# A704E.net
KiCad netlist of a schematic drawn in EAGLE
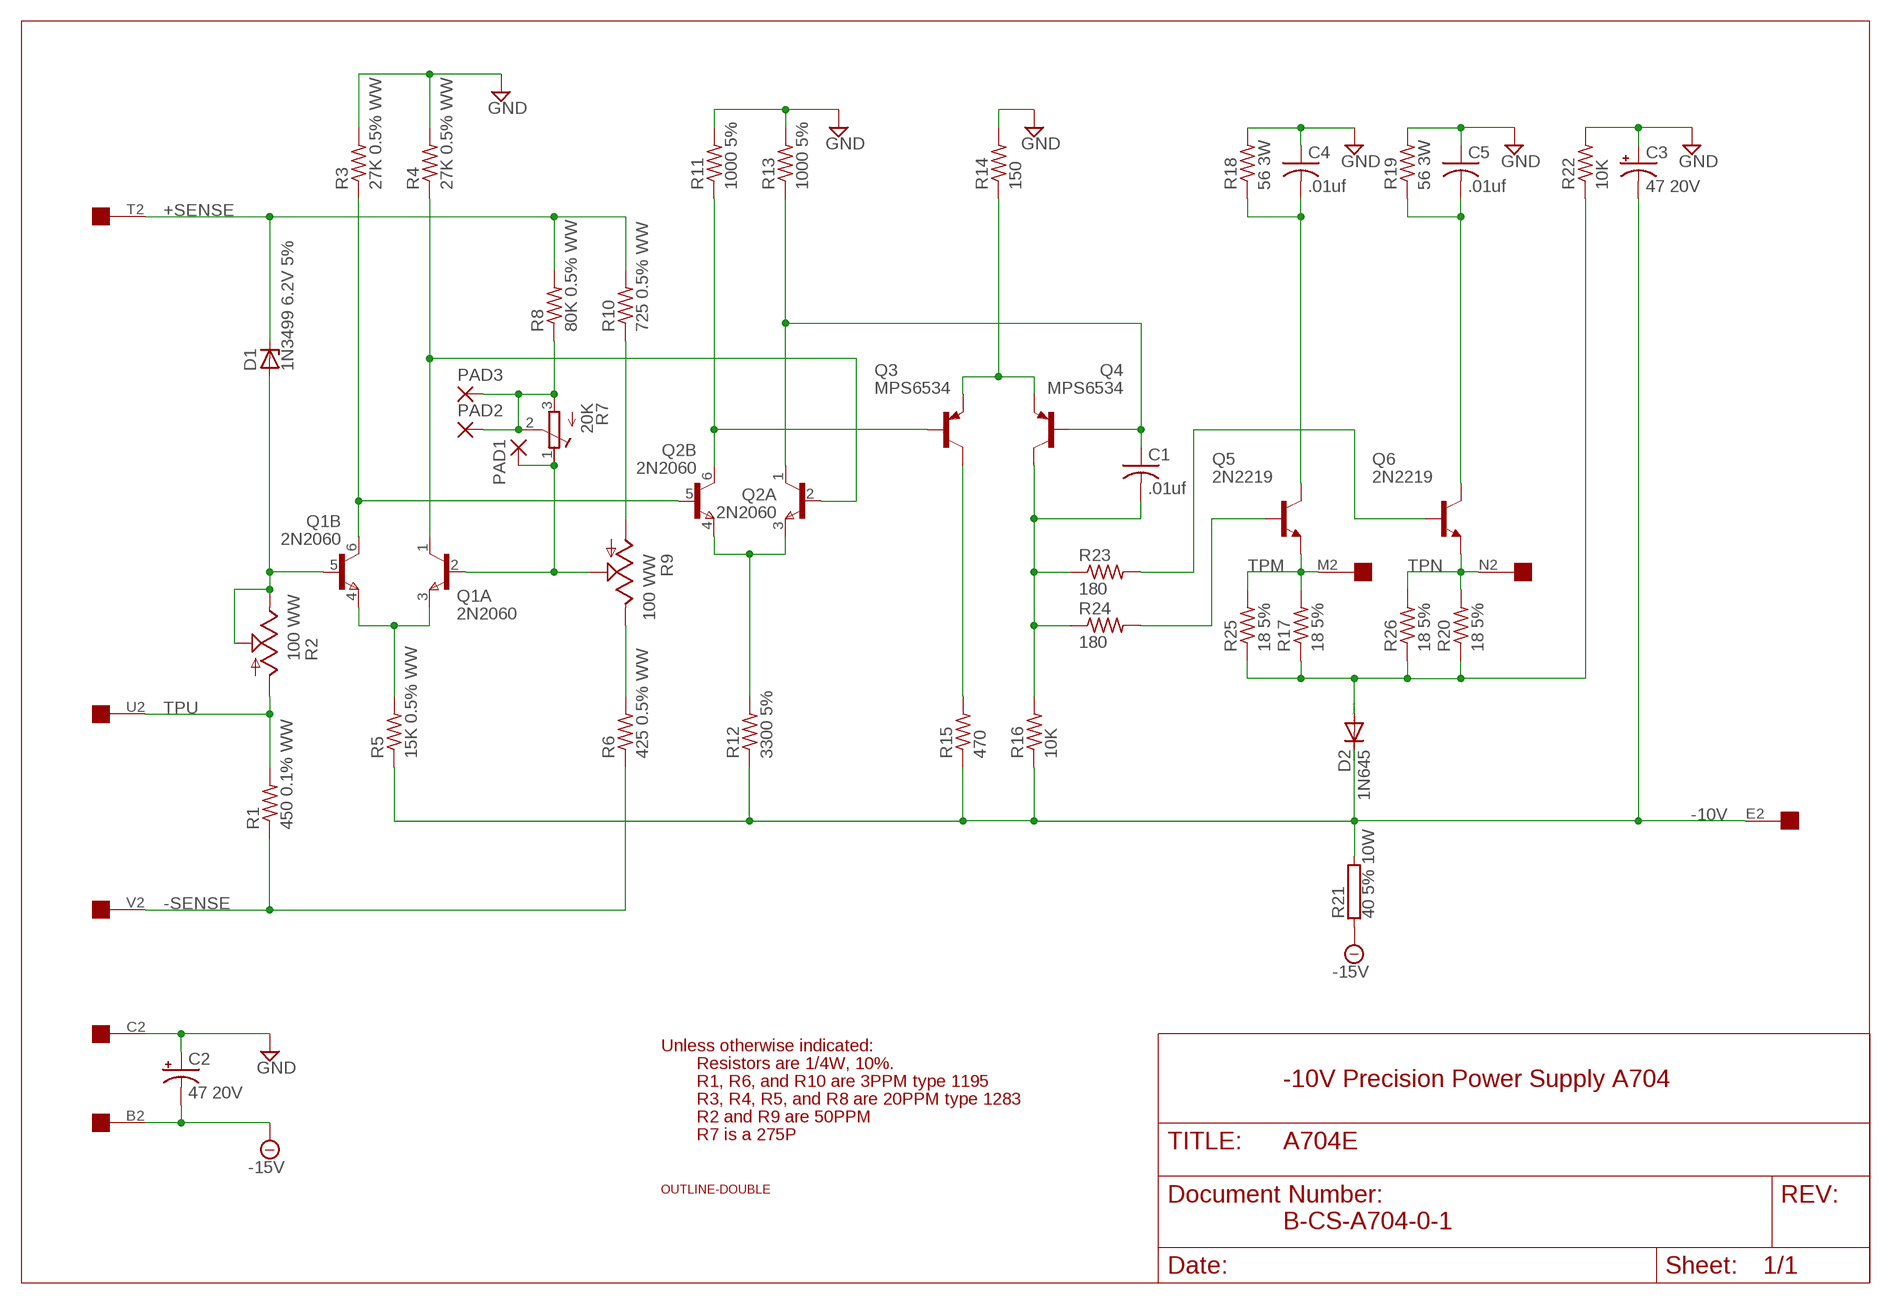
[diagram p0: schematic, sheet 1]

(export (version "E")
  (design (tool "Eeschema 10.0.6"))
  (components
    (comp (ref "C1")
      (value ".01uf")
      (footprint "eagle-import:C050-025X075")
      (libsource (lib "eagle-import") (part "C-US050-025X075"))
    )
    (comp (ref "C2")
      (value "47 20V")
      (footprint "eagle-import:E22-6")
      (libsource (lib "eagle-import") (part "CPOL-USE22-6AXIAL"))
    )
    (comp (ref "C3")
      (value "47 20V")
      (footprint "eagle-import:E22-6")
      (libsource (lib "eagle-import") (part "CPOL-USE22-6AXIAL"))
    )
    (comp (ref "C4")
      (value ".01uf")
      (footprint "eagle-import:C050-025X075")
      (libsource (lib "eagle-import") (part "C-US050-025X075"))
    )
    (comp (ref "C5")
      (value ".01uf")
      (footprint "eagle-import:C050-025X075")
      (libsource (lib "eagle-import") (part "C-US050-025X075"))
    )
    (comp (ref "D1")
      (value "1N3499 6.2V 5%")
      (footprint "eagle-import:DO35Z10")
      (libsource (lib "eagle-import") (part "ZENER-DIODEDO35Z10"))
    )
    (comp (ref "D2")
      (value "1N645")
      (footprint "eagle-import:DO35-10")
      (libsource (lib "eagle-import") (part "1N4148DO35-10"))
    )
    (comp (ref "PAD1")
      (value "2,54/1,0")
      (footprint "eagle-import:2,54_1,0")
      (libsource (lib "eagle-import") (part "2,54/1,0"))
    )
    (comp (ref "PAD2")
      (value "2,54/1,0")
      (footprint "eagle-import:2,54_1,0")
      (libsource (lib "eagle-import") (part "2,54/1,0"))
    )
    (comp (ref "PAD3")
      (value "2,54/1,0")
      (footprint "eagle-import:2,54_1,0")
      (libsource (lib "eagle-import") (part "2,54/1,0"))
    )
    (comp (ref "Q1")
      (value "2N2060")
      (footprint "eagle-import:TO78")
      (libsource (lib "eagle-import") (part "MAT-02H"))
    )
    (comp (ref "Q2")
      (value "2N2060")
      (footprint "eagle-import:TO78")
      (libsource (lib "eagle-import") (part "MAT-02H"))
    )
    (comp (ref "Q3")
      (value "MPS6534")
      (footprint "eagle-import:TO39")
      (libsource (lib "eagle-import") (part "2N2904A"))
    )
    (comp (ref "Q4")
      (value "MPS6534")
      (footprint "eagle-import:TO39")
      (libsource (lib "eagle-import") (part "2N2904A"))
    )
    (comp (ref "Q5")
      (value "2N2219")
      (footprint "eagle-import:TO39")
      (libsource (lib "eagle-import") (part "-NPN-TO39-EBC2N1613"))
    )
    (comp (ref "Q6")
      (value "2N2219")
      (footprint "eagle-import:TO39")
      (libsource (lib "eagle-import") (part "-NPN-TO39-EBC2N1613"))
    )
    (comp (ref "R1")
      (value "450 0.1% WW")
      (footprint "eagle-import:P0817_22")
      (libsource (lib "eagle-import") (part "R-US_0817/22"))
    )
    (comp (ref "R2")
      (value "100 WW")
      (footprint "eagle-import:S75P")
      (libsource (lib "eagle-import") (part "TRIM_US-S75P"))
    )
    (comp (ref "R3")
      (value "27K 0.5% WW")
      (footprint "eagle-import:0411_15")
      (libsource (lib "eagle-import") (part "R-US_0411/15"))
    )
    (comp (ref "R4")
      (value "27K 0.5% WW")
      (footprint "eagle-import:0411_15")
      (libsource (lib "eagle-import") (part "R-US_0411/15"))
    )
    (comp (ref "R5")
      (value "15K 0.5% WW")
      (footprint "eagle-import:0411_15")
      (libsource (lib "eagle-import") (part "R-US_0411/15"))
    )
    (comp (ref "R6")
      (value "425 0.5% WW")
      (footprint "eagle-import:P0817_22")
      (libsource (lib "eagle-import") (part "R-US_0817/22"))
    )
    (comp (ref "R7")
      (value "20K")
      (footprint "eagle-import:3006Y")
      (libsource (lib "eagle-import") (part "275P"))
    )
    (comp (ref "R8")
      (value "80K 0.5% WW")
      (footprint "eagle-import:0411_15")
      (libsource (lib "eagle-import") (part "R-US_0411/15"))
    )
    (comp (ref "R9")
      (value "100 WW")
      (footprint "eagle-import:S75P")
      (libsource (lib "eagle-import") (part "TRIM_US-S75P"))
    )
    (comp (ref "R10")
      (value "725 0.5% WW")
      (footprint "eagle-import:P0817_22")
      (libsource (lib "eagle-import") (part "R-US_0817/22"))
    )
    (comp (ref "R11")
      (value "1000 5%")
      (footprint "eagle-import:0207_10")
      (libsource (lib "eagle-import") (part "R-US_0207/10"))
    )
    (comp (ref "R12")
      (value "3300 5%")
      (footprint "eagle-import:0207_10")
      (libsource (lib "eagle-import") (part "R-US_0207/10"))
    )
    (comp (ref "R13")
      (value "1000 5%")
      (footprint "eagle-import:0207_10")
      (libsource (lib "eagle-import") (part "R-US_0207/10"))
    )
    (comp (ref "R14")
      (value "150")
      (footprint "eagle-import:0207_10")
      (libsource (lib "eagle-import") (part "R-US_0207/10"))
    )
    (comp (ref "R15")
      (value "470")
      (footprint "eagle-import:0207_10")
      (libsource (lib "eagle-import") (part "R-US_0207/10"))
    )
    (comp (ref "R16")
      (value "10K")
      (footprint "eagle-import:0207_10")
      (libsource (lib "eagle-import") (part "R-US_0207/10"))
    )
    (comp (ref "R17")
      (value "18 5%")
      (footprint "eagle-import:0207_10")
      (libsource (lib "eagle-import") (part "R-US_0207/10"))
    )
    (comp (ref "R18")
      (value "56 3W")
      (footprint "eagle-import:0411_15")
      (libsource (lib "eagle-import") (part "R-US_0411/15"))
    )
    (comp (ref "R19")
      (value "56 3W")
      (footprint "eagle-import:0411_15")
      (libsource (lib "eagle-import") (part "R-US_0411/15"))
    )
    (comp (ref "R20")
      (value "18 5%")
      (footprint "eagle-import:0207_10")
      (libsource (lib "eagle-import") (part "R-US_0207/10"))
    )
    (comp (ref "R21")
      (value "40 5% 10W")
      (footprint "eagle-import:KH216-8")
      (libsource (lib "eagle-import") (part "RKH216-8"))
    )
    (comp (ref "R22")
      (value "10K")
      (footprint "eagle-import:0207_10")
      (libsource (lib "eagle-import") (part "R-US_0207/10"))
    )
    (comp (ref "R23")
      (value "180")
      (footprint "eagle-import:0207_10")
      (libsource (lib "eagle-import") (part "R-US_0207/10"))
    )
    (comp (ref "R24")
      (value "180")
      (footprint "eagle-import:0207_10")
      (libsource (lib "eagle-import") (part "R-US_0207/10"))
    )
    (comp (ref "R25")
      (value "18 5%")
      (footprint "eagle-import:0207_10")
      (libsource (lib "eagle-import") (part "R-US_0207/10"))
    )
    (comp (ref "R26")
      (value "18 5%")
      (footprint "eagle-import:0207_10")
      (libsource (lib "eagle-import") (part "R-US_0207/10"))
    )
    (comp (ref "U$2")
      (value "OUTLINE-DOUBLE")
      (footprint "eagle-import:DOUBLE")
      (libsource (lib "eagle-import") (part "OUTLINE-DOUBLE"))
    )
    (comp (ref "U$3")
      (value "EDGE-1")
      (footprint "eagle-import:EDGE-CON1")
      (libsource (lib "eagle-import") (part "EDGE-1"))
    )
  )
  (nets
    (net (code "1") (name "-15V") (class "Default")
      (node (ref "C2") (pin "-") (pinfunction "-_-") (pintype "passive"))
      (node (ref "R21") (pin "1") (pinfunction "1_1") (pintype "passive"))
      (node (ref "U$3") (pin "B2") (pinfunction "1_B2") (pintype "bidirectional"))
    )
    (net (code "2") (name "/+SENSE") (class "Default")
      (node (ref "D1") (pin "C") (pinfunction "C_C") (pintype "passive"))
      (node (ref "R10") (pin "2") (pinfunction "2_2") (pintype "passive"))
      (node (ref "R8") (pin "2") (pinfunction "2_2") (pintype "passive"))
      (node (ref "U$3") (pin "T2") (pinfunction "1_T2") (pintype "bidirectional"))
    )
    (net (code "3") (name "/-10V") (class "Default")
      (node (ref "C3") (pin "-") (pinfunction "-_-") (pintype "passive"))
      (node (ref "D2") (pin "C") (pinfunction "C_C") (pintype "passive"))
      (node (ref "R12") (pin "1") (pinfunction "1_1") (pintype "passive"))
      (node (ref "R15") (pin "1") (pinfunction "1_1") (pintype "passive"))
      (node (ref "R16") (pin "1") (pinfunction "1_1") (pintype "passive"))
      (node (ref "R21") (pin "2") (pinfunction "2_2") (pintype "passive"))
      (node (ref "R5") (pin "1") (pinfunction "1_1") (pintype "passive"))
      (node (ref "U$3") (pin "E2") (pinfunction "1_E2") (pintype "bidirectional"))
    )
    (net (code "4") (name "/-SENSE") (class "Default")
      (node (ref "R1") (pin "1") (pinfunction "1_1") (pintype "passive"))
      (node (ref "R6") (pin "1") (pinfunction "1_1") (pintype "passive"))
      (node (ref "U$3") (pin "V2") (pinfunction "1_V2") (pintype "bidirectional"))
    )
    (net (code "5") (name "/TPM") (class "Default")
      (node (ref "Q5") (pin "1") (pinfunction "E_1") (pintype "passive"))
      (node (ref "R17") (pin "2") (pinfunction "2_2") (pintype "passive"))
      (node (ref "R25") (pin "2") (pinfunction "2_2") (pintype "passive"))
      (node (ref "U$3") (pin "M2") (pinfunction "1_M2") (pintype "bidirectional"))
    )
    (net (code "6") (name "/TPN") (class "Default")
      (node (ref "Q6") (pin "1") (pinfunction "E_1") (pintype "passive"))
      (node (ref "R20") (pin "2") (pinfunction "2_2") (pintype "passive"))
      (node (ref "R26") (pin "2") (pinfunction "2_2") (pintype "passive"))
      (node (ref "U$3") (pin "N2") (pinfunction "1_N2") (pintype "bidirectional"))
    )
    (net (code "7") (name "/TPU") (class "Default")
      (node (ref "R1") (pin "2") (pinfunction "2_2") (pintype "passive"))
      (node (ref "R2") (pin "A") (pinfunction "A_A") (pintype "passive"))
      (node (ref "U$3") (pin "U2") (pinfunction "1_U2") (pintype "bidirectional"))
    )
    (net (code "8") (name "GND") (class "Default")
      (node (ref "C2") (pin "+") (pinfunction "+_+") (pintype "passive"))
      (node (ref "C3") (pin "+") (pinfunction "+_+") (pintype "passive"))
      (node (ref "C4") (pin "1") (pinfunction "1_1") (pintype "passive"))
      (node (ref "C5") (pin "1") (pinfunction "1_1") (pintype "passive"))
      (node (ref "R11") (pin "2") (pinfunction "2_2") (pintype "passive"))
      (node (ref "R13") (pin "2") (pinfunction "2_2") (pintype "passive"))
      (node (ref "R14") (pin "2") (pinfunction "2_2") (pintype "passive"))
      (node (ref "R18") (pin "2") (pinfunction "2_2") (pintype "passive"))
      (node (ref "R19") (pin "2") (pinfunction "2_2") (pintype "passive"))
      (node (ref "R22") (pin "2") (pinfunction "2_2") (pintype "passive"))
      (node (ref "R3") (pin "2") (pinfunction "2_2") (pintype "passive"))
      (node (ref "R4") (pin "2") (pinfunction "2_2") (pintype "passive"))
      (node (ref "U$3") (pin "C2") (pinfunction "1_C2") (pintype "bidirectional"))
    )
    (net (code "9") (name "Net-(D2-PadA)") (class "Default")
      (node (ref "D2") (pin "A") (pinfunction "A_A") (pintype "passive"))
      (node (ref "R17") (pin "1") (pinfunction "1_1") (pintype "passive"))
      (node (ref "R20") (pin "1") (pinfunction "1_1") (pintype "passive"))
      (node (ref "R22") (pin "1") (pinfunction "1_1") (pintype "passive"))
      (node (ref "R25") (pin "1") (pinfunction "1_1") (pintype "passive"))
      (node (ref "R26") (pin "1") (pinfunction "1_1") (pintype "passive"))
    )
    (net (code "10") (name "Net-(PAD1-P)") (class "Default")
      (node (ref "PAD1") (pin "1") (pinfunction "P_1") (pintype "passive"))
      (node (ref "Q1") (pin "2") (pinfunction "B_2") (pintype "passive"))
      (node (ref "R7") (pin "1") (pinfunction "A_1") (pintype "passive"))
      (node (ref "R9") (pin "S") (pinfunction "S_S") (pintype "passive"))
    )
    (net (code "11") (name "Net-(PAD2-P)") (class "Default")
      (node (ref "PAD2") (pin "1") (pinfunction "P_1") (pintype "passive"))
      (node (ref "PAD3") (pin "1") (pinfunction "P_1") (pintype "passive"))
      (node (ref "R7") (pin "2") (pinfunction "S_2") (pintype "passive"))
      (node (ref "R7") (pin "3") (pinfunction "E_3") (pintype "passive"))
      (node (ref "R8") (pin "1") (pinfunction "1_1") (pintype "passive"))
    )
    (net (code "12") (name "Net-(Q1A-C)") (class "Default")
      (node (ref "Q1") (pin "1") (pinfunction "C_1") (pintype "passive"))
      (node (ref "Q2") (pin "2") (pinfunction "B_2") (pintype "passive"))
      (node (ref "R4") (pin "1") (pinfunction "1_1") (pintype "passive"))
    )
    (net (code "13") (name "Net-(Q1A-E)") (class "Default")
      (node (ref "Q1") (pin "3") (pinfunction "E_3") (pintype "passive"))
      (node (ref "Q1") (pin "4") (pinfunction "E_4") (pintype "passive"))
      (node (ref "R5") (pin "2") (pinfunction "2_2") (pintype "passive"))
    )
    (net (code "14") (name "Net-(Q1B-B)") (class "Default")
      (node (ref "D1") (pin "A") (pinfunction "A_A") (pintype "passive"))
      (node (ref "Q1") (pin "5") (pinfunction "B_5") (pintype "passive"))
      (node (ref "R2") (pin "E") (pinfunction "E_E") (pintype "passive"))
      (node (ref "R2") (pin "S") (pinfunction "S_S") (pintype "passive"))
    )
    (net (code "15") (name "Net-(Q1B-C)") (class "Default")
      (node (ref "Q1") (pin "6") (pinfunction "C_6") (pintype "passive"))
      (node (ref "Q2") (pin "5") (pinfunction "B_5") (pintype "passive"))
      (node (ref "R3") (pin "1") (pinfunction "1_1") (pintype "passive"))
    )
    (net (code "16") (name "Net-(Q2A-C)") (class "Default")
      (node (ref "C1") (pin "1") (pinfunction "1_1") (pintype "passive"))
      (node (ref "Q2") (pin "1") (pinfunction "C_1") (pintype "passive"))
      (node (ref "Q4") (pin "2") (pinfunction "B_2") (pintype "passive"))
      (node (ref "R13") (pin "1") (pinfunction "1_1") (pintype "passive"))
    )
    (net (code "17") (name "Net-(Q2A-E)") (class "Default")
      (node (ref "Q2") (pin "3") (pinfunction "E_3") (pintype "passive"))
      (node (ref "Q2") (pin "4") (pinfunction "E_4") (pintype "passive"))
      (node (ref "R12") (pin "2") (pinfunction "2_2") (pintype "passive"))
    )
    (net (code "18") (name "Net-(Q2B-C)") (class "Default")
      (node (ref "Q2") (pin "6") (pinfunction "C_6") (pintype "passive"))
      (node (ref "Q3") (pin "2") (pinfunction "B_2") (pintype "passive"))
      (node (ref "R11") (pin "1") (pinfunction "1_1") (pintype "passive"))
    )
    (net (code "19") (name "Net-(Q3-C)") (class "Default")
      (node (ref "Q3") (pin "3") (pinfunction "C_3") (pintype "passive"))
      (node (ref "R15") (pin "2") (pinfunction "2_2") (pintype "passive"))
    )
    (net (code "20") (name "Net-(Q3-E)") (class "Default")
      (node (ref "Q3") (pin "1") (pinfunction "E_1") (pintype "passive"))
      (node (ref "Q4") (pin "1") (pinfunction "E_1") (pintype "passive"))
      (node (ref "R14") (pin "1") (pinfunction "1_1") (pintype "passive"))
    )
    (net (code "21") (name "Net-(Q4-C)") (class "Default")
      (node (ref "C1") (pin "2") (pinfunction "2_2") (pintype "passive"))
      (node (ref "Q4") (pin "3") (pinfunction "C_3") (pintype "passive"))
      (node (ref "R16") (pin "2") (pinfunction "2_2") (pintype "passive"))
      (node (ref "R23") (pin "1") (pinfunction "1_1") (pintype "passive"))
      (node (ref "R24") (pin "1") (pinfunction "1_1") (pintype "passive"))
    )
    (net (code "22") (name "Net-(Q5-B)") (class "Default")
      (node (ref "Q5") (pin "2") (pinfunction "B_2") (pintype "passive"))
      (node (ref "R24") (pin "2") (pinfunction "2_2") (pintype "passive"))
    )
    (net (code "23") (name "Net-(Q5-C)") (class "Default")
      (node (ref "C4") (pin "2") (pinfunction "2_2") (pintype "passive"))
      (node (ref "Q5") (pin "3") (pinfunction "C_3") (pintype "passive"))
      (node (ref "R18") (pin "1") (pinfunction "1_1") (pintype "passive"))
    )
    (net (code "24") (name "Net-(Q6-B)") (class "Default")
      (node (ref "Q6") (pin "2") (pinfunction "B_2") (pintype "passive"))
      (node (ref "R23") (pin "2") (pinfunction "2_2") (pintype "passive"))
    )
    (net (code "25") (name "Net-(Q6-C)") (class "Default")
      (node (ref "C5") (pin "2") (pinfunction "2_2") (pintype "passive"))
      (node (ref "Q6") (pin "3") (pinfunction "C_3") (pintype "passive"))
      (node (ref "R19") (pin "1") (pinfunction "1_1") (pintype "passive"))
    )
    (net (code "26") (name "Net-(R6-Pad2)") (class "Default")
      (node (ref "R6") (pin "2") (pinfunction "2_2") (pintype "passive"))
      (node (ref "R9") (pin "E") (pinfunction "E_E") (pintype "passive"))
    )
    (net (code "27") (name "Net-(R10-Pad1)") (class "Default")
      (node (ref "R10") (pin "1") (pinfunction "1_1") (pintype "passive"))
      (node (ref "R9") (pin "A") (pinfunction "A_A") (pintype "passive"))
    )
  )
)
